# STM32F103_MCU.net
KiCad netlist of a schematic drawn in Altium Designer
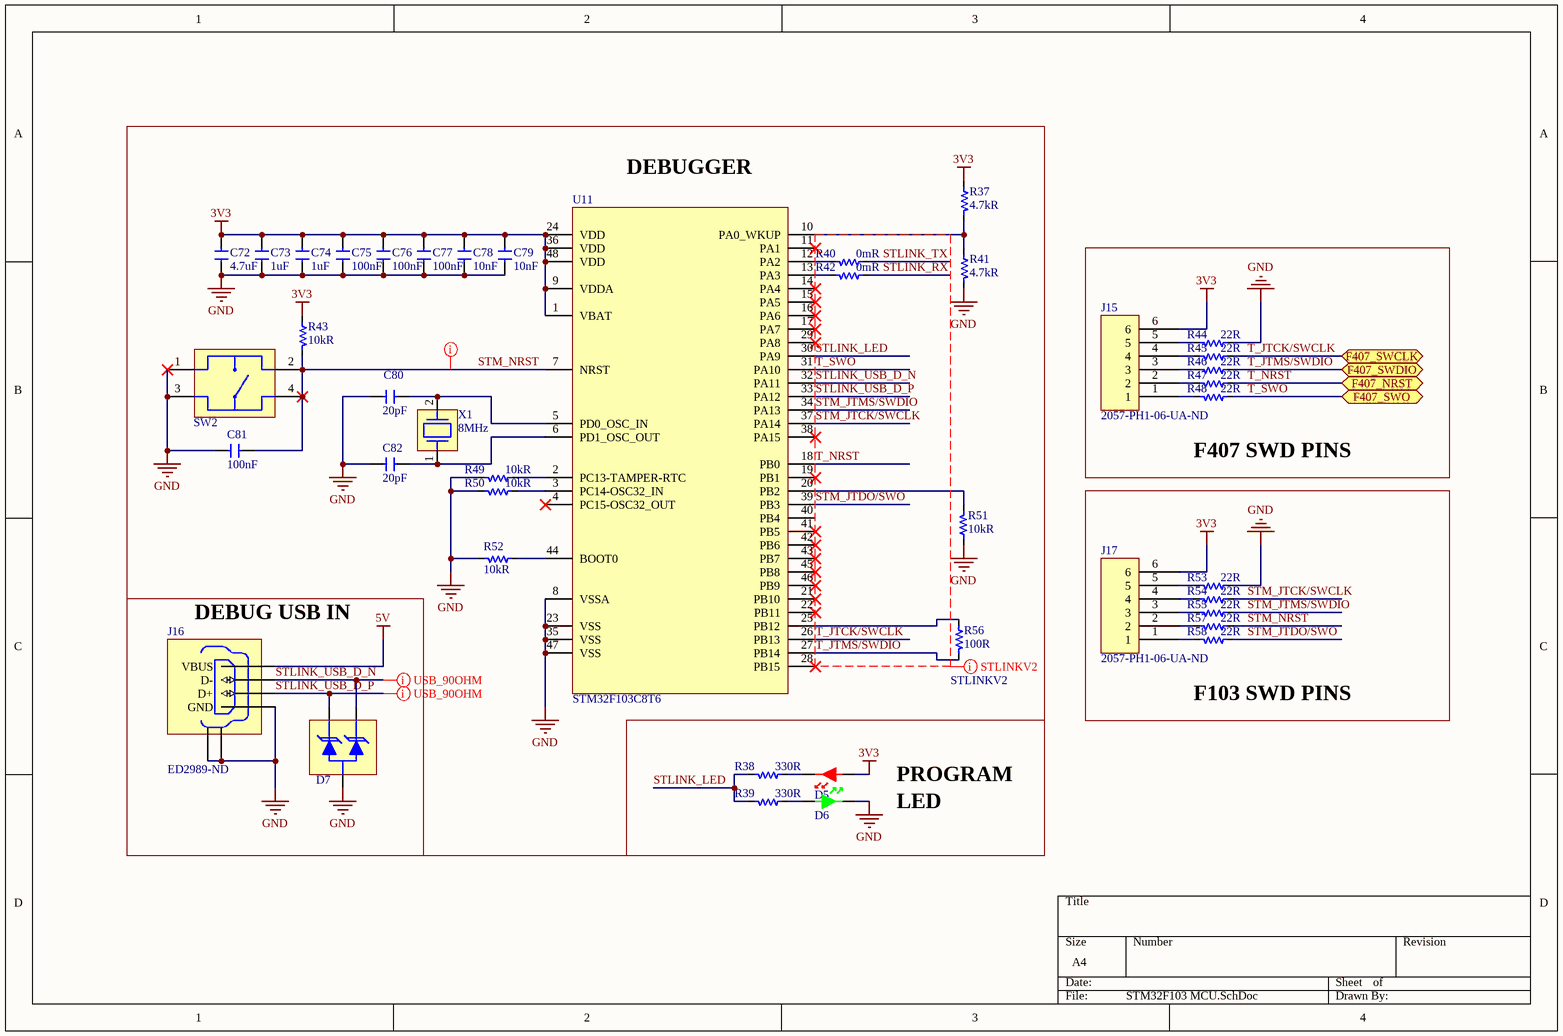
[diagram p0: STM32F103 MCU.SchDoc]

(export (version "E")
  (design (tool "Eeschema 10.0.6"))
  (components
    (comp (ref "C72")
      (value "CAP_4.7uF_%10_0805_25V_X7R_CER")
      (footprint "0805_CAP")
      (description "Cap 4.7UF 25VDC X7R 10% SMD 0805 Embossed Tape")
      (fields
        (field (name "MANUFACTURER") "Murata")
        (field (name "MANUFACTURER PART NUMBER") "GRM21BZ71E475KE15L")
        (field (name "CAPACITANCE") "4.7uF")
      )
      (libsource (lib "Main Schematic Library") (part "CAP_4.7uF_%10_0805_25V_X7R_CER"))
    )
    (comp (ref "C73")
      (value "1uF")
      (footprint "0805_CAP")
      (description "陶瓷电容 1uF(105) 1uF ±10% 25V 0805")
      (fields
        (field (name "MANUFACTURER") "Samsung")
        (field (name "MANUFACTURER PART NUMBER") "CL21B105KAFNNNG")
      )
      (libsource (lib "Main Schematic Library") (part "CAP_1uF_%10_25V_0805_X7R_CER"))
    )
    (comp (ref "C74")
      (value "1uF")
      (footprint "0805_CAP")
      (description "陶瓷电容 1uF(105) 1uF ±10% 25V 0805")
      (fields
        (field (name "MANUFACTURER") "Samsung")
        (field (name "MANUFACTURER PART NUMBER") "CL21B105KAFNNNG")
      )
      (libsource (lib "Main Schematic Library") (part "CAP_1uF_%10_25V_0805_X7R_CER"))
    )
    (comp (ref "C75")
      (value "CAP_0.1uF_%20_50V_0805_X7R_CER")
      (footprint "0805_CAP")
      (description "Cap Ceramic 0.1uF 50V X7R 20% SMD 0805 125C Paper T/R")
      (fields
        (field (name "MANUFACTURER") "KEMET")
        (field (name "MANUFACTURER PART NUMBER") "C0805C104M5RACTU")
        (field (name "CAPACITANCE") "100nF")
      )
      (libsource (lib "Main Schematic Library") (part "CAP_0.1uF_%20_50V_0805_X7R_CER"))
    )
    (comp (ref "C76")
      (value "CAP_0.1uF_%20_50V_0805_X7R_CER")
      (footprint "0805_CAP")
      (description "Cap Ceramic 0.1uF 50V X7R 20% SMD 0805 125C Paper T/R")
      (fields
        (field (name "MANUFACTURER") "KEMET")
        (field (name "MANUFACTURER PART NUMBER") "C0805C104M5RACTU")
        (field (name "CAPACITANCE") "100nF")
      )
      (libsource (lib "Main Schematic Library") (part "CAP_0.1uF_%20_50V_0805_X7R_CER"))
    )
    (comp (ref "C77")
      (value "CAP_0.1uF_%20_50V_0805_X7R_CER")
      (footprint "0805_CAP")
      (description "Cap Ceramic 0.1uF 50V X7R 20% SMD 0805 125C Paper T/R")
      (fields
        (field (name "MANUFACTURER") "KEMET")
        (field (name "MANUFACTURER PART NUMBER") "C0805C104M5RACTU")
        (field (name "CAPACITANCE") "100nF")
      )
      (libsource (lib "Main Schematic Library") (part "CAP_0.1uF_%20_50V_0805_X7R_CER"))
    )
    (comp (ref "C78")
      (value "CAP_10nF_%10_50V_0805_X7R_CER")
      (footprint "0805_CAP")
      (description "CAP CER 10000PF 50V X7R 0805")
      (fields
        (field (name "MANUFACTURER") "Samsung")
        (field (name "MANUFACTURER PART NUMBER") "CL21B103KBANNNC")
        (field (name "CAPACITANCE") "10nF")
      )
      (libsource (lib "Main Schematic Library") (part "CAP_10nF_%10_50V_0805_X7R_CER"))
    )
    (comp (ref "C79")
      (value "CAP_10nF_%10_50V_0805_X7R_CER")
      (footprint "0805_CAP")
      (description "CAP CER 10000PF 50V X7R 0805")
      (fields
        (field (name "MANUFACTURER") "Samsung")
        (field (name "MANUFACTURER PART NUMBER") "CL21B103KBANNNC")
        (field (name "CAPACITANCE") "10nF")
      )
      (libsource (lib "Main Schematic Library") (part "CAP_10nF_%10_50V_0805_X7R_CER"))
    )
    (comp (ref "C80")
      (value "CAP_20pF_5%_50V_0805_C0G/NP0_CER")
      (footprint "0805_CAP")
      (description "CAP CER 20PF 50V C0G/NP0 0805")
      (fields
        (field (name "MANUFACTURER") "Samsung")
        (field (name "MANUFACTURER PART NUMBER") "CL21C200JBANNNC")
        (field (name "CAPACITANCE") "20pF")
      )
      (libsource (lib "Main Schematic Library") (part "CAP_20pF_5%_50V_0805_C0G/NP0_CER"))
    )
    (comp (ref "C81")
      (value "CAP_100nF_50V_0805_C0G_CER")
      (footprint "0805_CAP")
      (description "Cap Ceramic 0.1uF 50V X7R 20% SMD 0805 125C Paper T/R")
      (fields
        (field (name "MANUFACTURER") "KEMET")
        (field (name "MANUFACTURER PART NUMBER") "C0805C104M5RACTU")
        (field (name "CAPACITANCE") "100nF")
      )
      (libsource (lib "Main Schematic Library") (part "CAP_100nF_50V_0805_C0G_CER"))
    )
    (comp (ref "C82")
      (value "CAP_20pF_5%_50V_0805_C0G/NP0_CER")
      (footprint "0805_CAP")
      (description "CAP CER 20PF 50V C0G/NP0 0805")
      (fields
        (field (name "MANUFACTURER") "Samsung")
        (field (name "MANUFACTURER PART NUMBER") "CL21C200JBANNNC")
        (field (name "CAPACITANCE") "20pF")
      )
      (libsource (lib "Main Schematic Library") (part "CAP_20pF_5%_50V_0805_C0G/NP0_CER"))
    )
    (comp (ref "D5")
      (value "Red")
      (footprint "DIOC2114X07N-0805-LED-RED")
      (description "Led Red Clear 2SMD")
      (fields
        (field (name "MANUFACTURER") "Everlight")
        (field (name "MANUFACTURER PART NUMBER") "EAST2012RA1")
      )
      (libsource (lib "Main Schematic Library") (part "LED_RED CLEAR_2SMD/0805"))
    )
    (comp (ref "D6")
      (value "Green")
      (footprint "DIOC2114X07N-0805-LED-GREEN")
      (description "Led Green Clear 2SMD")
      (fields
        (field (name "MANUFACTURER") "Everlight")
        (field (name "MANUFACTURER PART NUMBER") "EAST2012GA5")
      )
      (libsource (lib "Main Schematic Library") (part "LED_GREEN CLEAR_2SMD/0805"))
    )
    (comp (ref "D7")
      (value "DIODE_TVS_3.3VWM_8VC_SOT23")
      (footprint "SOT170P237X110-3N")
      (description "ESD Suppressor TVS Uni-Dir 3.3V 3-Pin SOT-23 T/R")
      (fields (field (name "MANUFACTURER") "MCC") (field (name "MANUFACTURER PART NUMBER") "ESD3V3AP-TP"))
      (libsource (lib "Main Schematic Library") (part "DIODE_TVS_3.3VWM_8VC_SOT23"))
    )
    (comp (ref "J15")
      (value "CONN_1X6_2.54m_Male Header")
      (footprint "DIP_1X6_MALE_HEADER_2.54_PITCH")
      (description "PH Series 6 Position Through Hole Single Row Straight .100 Header")
      (fields
        (field (name "MANUFACTURER") "Adam Equipment")
        (field (name "MANUFACTURER PART NUMBER") "PH1-06-UA")
        (field (name "SUPPLIER PART NUMBER 1") "2057-PH1-06-UA-ND")
      )
      (libsource (lib "Main Schematic Library") (part "CONN_1X6_2.54m_Male Header"))
    )
    (comp (ref "J16")
      (value "CONN_RCPT_USB-TYPE A_A1HSW6")
      (footprint "USB_2.0_B_OST_USB-A1HSW6")
      (description "USB - A Receptacle Connector 4 Position Through Hole, Right Angle")
      (fields
        (field (name "MP") "USB-A1HSW6")
        (field (name "MF") "{'manufacturer': u'On Shore'}")
        (field (name "SUPPLIER PART NUMBER 1") "ED2989-ND")
      )
      (libsource (lib "Main Schematic Library") (part "CONN_RCPT_USB-TYPE A_A1HSW6"))
    )
    (comp (ref "J17")
      (value "CONN_1X6_2.54m_Male Header")
      (footprint "DIP_1X6_MALE_HEADER_2.54_PITCH")
      (description "PH Series 6 Position Through Hole Single Row Straight .100 Header")
      (fields
        (field (name "MANUFACTURER") "Adam Equipment")
        (field (name "MANUFACTURER PART NUMBER") "PH1-06-UA")
        (field (name "SUPPLIER PART NUMBER 1") "2057-PH1-06-UA-ND")
      )
      (libsource (lib "Main Schematic Library") (part "CONN_1X6_2.54m_Male Header"))
    )
    (comp (ref "R37")
      (value "RES_4.7K OHM_5%_1/8W_0805")
      (footprint "0805_RES")
      (description "Res Thick Film 0805 4.7K Ohm 5% 1/8W ±200ppm/°C Molded SMD Paper T/R")
      (fields
        (field (name "MANUFACTURER") "Vishay")
        (field (name "MANUFACTURER PART NUMBER") "CRCW08054K70JNEAC")
        (field (name "RESISTANCE") "4.7kR")
      )
      (libsource (lib "Main Schematic Library") (part "RES_4.7K OHM_5%_1/8W_0805"))
    )
    (comp (ref "R38")
      (value "RES_330 OHM_5%_0805_1/8W")
      (footprint "0805_RES")
      (description "Res Thick Film 0805 330 Ohm 5% 0.125W(1/8W) ±100ppm/C Pad SMD Automotive T/R")
      (fields
        (field (name "MANUFACTURER") "TE Connectivity")
        (field (name "MANUFACTURER PART NUMBER") "CRGCQ0805J330R")
        (field (name "RESISTANCE") "330R")
      )
      (libsource (lib "Main Schematic Library") (part "RES_330 OHM_5%_0805_1/8W"))
    )
    (comp (ref "R39")
      (value "RES_330 OHM_5%_0805_1/8W")
      (footprint "0805_RES")
      (description "Res Thick Film 0805 330 Ohm 5% 0.125W(1/8W) ±100ppm/C Pad SMD Automotive T/R")
      (fields
        (field (name "MANUFACTURER") "TE Connectivity")
        (field (name "MANUFACTURER PART NUMBER") "CRGCQ0805J330R")
        (field (name "RESISTANCE") "330R")
      )
      (libsource (lib "Main Schematic Library") (part "RES_330 OHM_5%_0805_1/8W"))
    )
    (comp (ref "R40")
      (value "RES_0 OHM_JUMPER_0805_1/8W")
      (footprint "0805_RES")
      (description "贴片电阻 0Ω ±5% 1/8W 0805")
      (fields
        (field (name "MANUFACTURER") "Yageo")
        (field (name "MANUFACTURER PART NUMBER") "RC0805JR-070RL")
        (field (name "RESISTANCE") "0mR")
      )
      (libsource (lib "Main Schematic Library") (part "RES_0 OHM_JUMPER_0805_1/8W"))
    )
    (comp (ref "R41")
      (value "RES_4.7K OHM_5%_1/8W_0805")
      (footprint "0805_RES")
      (description "Res Thick Film 0805 4.7K Ohm 5% 1/8W ±200ppm/°C Molded SMD Paper T/R")
      (fields
        (field (name "MANUFACTURER") "Vishay")
        (field (name "MANUFACTURER PART NUMBER") "CRCW08054K70JNEAC")
        (field (name "RESISTANCE") "4.7kR")
      )
      (libsource (lib "Main Schematic Library") (part "RES_4.7K OHM_5%_1/8W_0805"))
    )
    (comp (ref "R42")
      (value "RES_0 OHM_JUMPER_0805_1/8W")
      (footprint "0805_RES")
      (description "贴片电阻 0Ω ±5% 1/8W 0805")
      (fields
        (field (name "MANUFACTURER") "Yageo")
        (field (name "MANUFACTURER PART NUMBER") "RC0805JR-070RL")
        (field (name "RESISTANCE") "0mR")
      )
      (libsource (lib "Main Schematic Library") (part "RES_0 OHM_JUMPER_0805_1/8W"))
    )
    (comp (ref "R43")
      (value "10k Ohms")
      (footprint "0805_RES")
      (description "Res SMD 0805 10K 1% 0.125W T.C.100PPM")
      (fields
        (field (name "MANUFACTURER") "TDK")
        (field (name "MANUFACTURER PART NUMBER") "C2012X7R1H104K085AA")
        (field (name "RESISTANCE") "10kR")
      )
      (libsource (lib "Main Schematic Library") (part "RES_10K OHM_%1_0805_1/8W"))
    )
    (comp (ref "R44")
      (value "RES_22 OHM_1%_1/8W_0805")
      (footprint "0805_RES")
      (description "Res Thick Film 0805 22 Ohm 1% 0.125W(1/8W) ±100ppm/C Pad SMD T/R")
      (fields
        (field (name "MANUFACTURER") "Vishay Dale")
        (field (name "MANUFACTURER PART NUMBER") "CRCW080522R0FKEAC")
        (field (name "RESISTANCE") "22R")
      )
      (libsource (lib "Main Schematic Library") (part "RES_22 OHM_1%_1/8W_0805"))
    )
    (comp (ref "R45")
      (value "RES_22 OHM_1%_1/8W_0805")
      (footprint "0805_RES")
      (description "Res Thick Film 0805 22 Ohm 1% 0.125W(1/8W) ±100ppm/C Pad SMD T/R")
      (fields
        (field (name "MANUFACTURER") "Vishay Dale")
        (field (name "MANUFACTURER PART NUMBER") "CRCW080522R0FKEAC")
        (field (name "RESISTANCE") "22R")
      )
      (libsource (lib "Main Schematic Library") (part "RES_22 OHM_1%_1/8W_0805"))
    )
    (comp (ref "R46")
      (value "RES_22 OHM_1%_1/8W_0805")
      (footprint "0805_RES")
      (description "Res Thick Film 0805 22 Ohm 1% 0.125W(1/8W) ±100ppm/C Pad SMD T/R")
      (fields
        (field (name "MANUFACTURER") "Vishay Dale")
        (field (name "MANUFACTURER PART NUMBER") "CRCW080522R0FKEAC")
        (field (name "RESISTANCE") "22R")
      )
      (libsource (lib "Main Schematic Library") (part "RES_22 OHM_1%_1/8W_0805"))
    )
    (comp (ref "R47")
      (value "RES_22 OHM_1%_1/8W_0805")
      (footprint "0805_RES")
      (description "Res Thick Film 0805 22 Ohm 1% 0.125W(1/8W) ±100ppm/C Pad SMD T/R")
      (fields
        (field (name "MANUFACTURER") "Vishay Dale")
        (field (name "MANUFACTURER PART NUMBER") "CRCW080522R0FKEAC")
        (field (name "RESISTANCE") "22R")
      )
      (libsource (lib "Main Schematic Library") (part "RES_22 OHM_1%_1/8W_0805"))
    )
    (comp (ref "R48")
      (value "RES_22 OHM_1%_1/8W_0805")
      (footprint "0805_RES")
      (description "Res Thick Film 0805 22 Ohm 1% 0.125W(1/8W) ±100ppm/C Pad SMD T/R")
      (fields
        (field (name "MANUFACTURER") "Vishay Dale")
        (field (name "MANUFACTURER PART NUMBER") "CRCW080522R0FKEAC")
        (field (name "RESISTANCE") "22R")
      )
      (libsource (lib "Main Schematic Library") (part "RES_22 OHM_1%_1/8W_0805"))
    )
    (comp (ref "R49")
      (value "10k Ohms")
      (footprint "0805_RES")
      (description "Res SMD 0805 10K 1% 0.125W T.C.100PPM")
      (fields
        (field (name "MANUFACTURER") "TDK")
        (field (name "MANUFACTURER PART NUMBER") "C2012X7R1H104K085AA")
        (field (name "RESISTANCE") "10kR")
      )
      (libsource (lib "Main Schematic Library") (part "RES_10K OHM_%1_0805_1/8W"))
    )
    (comp (ref "R50")
      (value "10k Ohms")
      (footprint "0805_RES")
      (description "Res SMD 0805 10K 1% 0.125W T.C.100PPM")
      (fields
        (field (name "MANUFACTURER") "TDK")
        (field (name "MANUFACTURER PART NUMBER") "C2012X7R1H104K085AA")
        (field (name "RESISTANCE") "10kR")
      )
      (libsource (lib "Main Schematic Library") (part "RES_10K OHM_%1_0805_1/8W"))
    )
    (comp (ref "R51")
      (value "10k Ohms")
      (footprint "0805_RES")
      (description "Res SMD 0805 10K 1% 0.125W T.C.100PPM")
      (fields
        (field (name "MANUFACTURER") "TDK")
        (field (name "MANUFACTURER PART NUMBER") "C2012X7R1H104K085AA")
        (field (name "RESISTANCE") "10kR")
      )
      (libsource (lib "Main Schematic Library") (part "RES_10K OHM_%1_0805_1/8W"))
    )
    (comp (ref "R52")
      (value "10k Ohms")
      (footprint "0805_RES")
      (description "Res SMD 0805 10K 1% 0.125W T.C.100PPM")
      (fields
        (field (name "MANUFACTURER") "TDK")
        (field (name "MANUFACTURER PART NUMBER") "C2012X7R1H104K085AA")
        (field (name "RESISTANCE") "10kR")
      )
      (libsource (lib "Main Schematic Library") (part "RES_10K OHM_%1_0805_1/8W"))
    )
    (comp (ref "R53")
      (value "RES_22 OHM_1%_1/8W_0805")
      (footprint "0805_RES")
      (description "Res Thick Film 0805 22 Ohm 1% 0.125W(1/8W) ±100ppm/C Pad SMD T/R")
      (fields
        (field (name "MANUFACTURER") "Vishay Dale")
        (field (name "MANUFACTURER PART NUMBER") "CRCW080522R0FKEAC")
        (field (name "RESISTANCE") "22R")
      )
      (libsource (lib "Main Schematic Library") (part "RES_22 OHM_1%_1/8W_0805"))
    )
    (comp (ref "R54")
      (value "RES_22 OHM_1%_1/8W_0805")
      (footprint "0805_RES")
      (description "Res Thick Film 0805 22 Ohm 1% 0.125W(1/8W) ±100ppm/C Pad SMD T/R")
      (fields
        (field (name "MANUFACTURER") "Vishay Dale")
        (field (name "MANUFACTURER PART NUMBER") "CRCW080522R0FKEAC")
        (field (name "RESISTANCE") "22R")
      )
      (libsource (lib "Main Schematic Library") (part "RES_22 OHM_1%_1/8W_0805"))
    )
    (comp (ref "R55")
      (value "RES_22 OHM_1%_1/8W_0805")
      (footprint "0805_RES")
      (description "Res Thick Film 0805 22 Ohm 1% 0.125W(1/8W) ±100ppm/C Pad SMD T/R")
      (fields
        (field (name "MANUFACTURER") "Vishay Dale")
        (field (name "MANUFACTURER PART NUMBER") "CRCW080522R0FKEAC")
        (field (name "RESISTANCE") "22R")
      )
      (libsource (lib "Main Schematic Library") (part "RES_22 OHM_1%_1/8W_0805"))
    )
    (comp (ref "R56")
      (value "RES_100 OHM_1%_0805_1/8W")
      (footprint "0805_RES")
      (description "贴片电阻 100Ω ± 1.00% 0.125W ± 100ppm/℃ 0805")
      (fields
        (field (name "MANUFACTURER") "Yageo")
        (field (name "MANUFACTURER PART NUMBER") "RC0805FR-07100RL")
        (field (name "RESISTANCE") "100R")
      )
      (libsource (lib "Main Schematic Library") (part "RES_100 OHM_1%_0805_1/8W"))
    )
    (comp (ref "R57")
      (value "RES_22 OHM_1%_1/8W_0805")
      (footprint "0805_RES")
      (description "Res Thick Film 0805 22 Ohm 1% 0.125W(1/8W) ±100ppm/C Pad SMD T/R")
      (fields
        (field (name "MANUFACTURER") "Vishay Dale")
        (field (name "MANUFACTURER PART NUMBER") "CRCW080522R0FKEAC")
        (field (name "RESISTANCE") "22R")
      )
      (libsource (lib "Main Schematic Library") (part "RES_22 OHM_1%_1/8W_0805"))
    )
    (comp (ref "R58")
      (value "RES_22 OHM_1%_1/8W_0805")
      (footprint "0805_RES")
      (description "Res Thick Film 0805 22 Ohm 1% 0.125W(1/8W) ±100ppm/C Pad SMD T/R")
      (fields
        (field (name "MANUFACTURER") "Vishay Dale")
        (field (name "MANUFACTURER PART NUMBER") "CRCW080522R0FKEAC")
        (field (name "RESISTANCE") "22R")
      )
      (libsource (lib "Main Schematic Library") (part "RES_22 OHM_1%_1/8W_0805"))
    )
    (comp (ref "SW2")
      (value "SWITCH_TACTILE_SPST-NO_0.05A_12V")
      (footprint "TACT_SWITCH_6MMX6MM")
      (description "Switch Tactile N.O. SPST Round Button Gull Wing 0.05A 12VDC 100000Cycles 1.27N SMD T/R")
      (fields
        (field (name "MANUFACTURER") "ITT C&K")
        (field (name "MANUFACTURER PART NUMBER") "PTS645SL43SMTR92LFS")
      )
      (libsource (lib "Main Schematic Library") (part "SWITCH_TACTILE_SPST-NO_0.05A_12V"))
    )
    (comp (ref "U11")
      (value "STM32F103C8T6")
      (footprint "QFP50P900X900X160-48N")
      (description "IC MCU 32BIT 64KB FLASH 48LQFP")
      (fields (field (name "MANUFACTURER") "STMicroelectronics"))
      (libsource (lib "Main Schematic Library") (part "IC_MCU_STM32F103C8T6"))
    )
    (comp (ref "X1")
      (value "8MHz")
      (footprint "HC-49/US")
      (description "Crystal 8.0000MHZ 16PF SMD")
      (fields
        (field (name "MANUFACTURER") "Raltron Electronics")
        (field (name "MANUFACTURER PART NUMBER") "AS-8.000-16-SMD-TR")
      )
      (libsource (lib "Main Schematic Library") (part "CRYSTAL_8.0000MHZ_16PF_SMD"))
    )
  )
  (nets
    (net (code "1") (name "/STLINK_LED") (class "Default")
      (node (ref "R38") (pin "1") (pinfunction "1_1") (pintype "passive"))
      (node (ref "R39") (pin "1") (pinfunction "1_1") (pintype "passive"))
      (node (ref "U11") (pin "30") (pinfunction "PA9_30") (pintype "passive"))
    )
    (net (code "2") (name "/STLINK_RX") (class "Default")
      (node (ref "R42") (pin "2") (pinfunction "2_2") (pintype "passive"))
    )
    (net (code "3") (name "/STLINK_TX") (class "Default")
      (node (ref "R40") (pin "2") (pinfunction "2_2") (pintype "passive"))
    )
    (net (code "4") (name "/STLINK_USB_D_N") (class "Default")
      (node (ref "D7") (pin "1") (pinfunction "CATHODE_1_1") (pintype "passive"))
      (node (ref "J16") (pin "2") (pinfunction "D-_2") (pintype "bidirectional"))
      (node (ref "U11") (pin "32") (pinfunction "PA11_32") (pintype "passive"))
    )
    (net (code "5") (name "/STLINK_USB_D_P") (class "Default")
      (node (ref "D7") (pin "2") (pinfunction "CATHODE_2_2") (pintype "passive"))
      (node (ref "J16") (pin "3") (pinfunction "D+_3") (pintype "bidirectional"))
      (node (ref "U11") (pin "33") (pinfunction "PA12_33") (pintype "passive"))
    )
    (net (code "6") (name "/STM_JTCK{slash}SWCLK") (class "Default")
      (node (ref "R54") (pin "2") (pinfunction "2_2") (pintype "passive"))
      (node (ref "U11") (pin "37") (pinfunction "PA14_37") (pintype "passive"))
    )
    (net (code "7") (name "/STM_JTDO{slash}SWO") (class "Default")
      (node (ref "R58") (pin "2") (pinfunction "2_2") (pintype "passive"))
      (node (ref "U11") (pin "39") (pinfunction "PB3_39") (pintype "passive"))
    )
    (net (code "8") (name "/STM_JTMS{slash}SWDIO") (class "Default")
      (node (ref "R55") (pin "2") (pinfunction "2_2") (pintype "passive"))
      (node (ref "U11") (pin "34") (pinfunction "PA13_34") (pintype "passive"))
    )
    (net (code "9") (name "/STM_NRST") (class "Default")
      (node (ref "C81") (pin "1") (pinfunction "1_1") (pintype "passive"))
      (node (ref "R43") (pin "1") (pinfunction "1_1") (pintype "passive"))
      (node (ref "R57") (pin "2") (pinfunction "2_2") (pintype "passive"))
      (node (ref "SW2") (pin "2") (pinfunction "2_2") (pintype "passive"))
      (node (ref "SW2") (pin "4") (pinfunction "4_4") (pintype "passive"))
      (node (ref "U11") (pin "7") (pinfunction "NRST_7") (pintype "passive"))
    )
    (net (code "10") (name "/T_JTCK{slash}SWCLK") (class "Default")
      (node (ref "R45") (pin "2") (pinfunction "2_2") (pintype "passive"))
      (node (ref "U11") (pin "26") (pinfunction "PB13_26") (pintype "passive"))
    )
    (net (code "11") (name "/T_JTMS{slash}SWDIO") (class "Default")
      (node (ref "R46") (pin "2") (pinfunction "2_2") (pintype "passive"))
      (node (ref "R56") (pin "1") (pinfunction "1_1") (pintype "passive"))
      (node (ref "U11") (pin "27") (pinfunction "PB14_27") (pintype "passive"))
    )
    (net (code "12") (name "/T_NRST") (class "Default")
      (node (ref "R47") (pin "2") (pinfunction "2_2") (pintype "passive"))
      (node (ref "U11") (pin "18") (pinfunction "PB0_18") (pintype "passive"))
    )
    (net (code "13") (name "/T_SWO") (class "Default")
      (node (ref "R48") (pin "2") (pinfunction "2_2") (pintype "passive"))
      (node (ref "U11") (pin "31") (pinfunction "PA10_31") (pintype "passive"))
    )
    (net (code "14") (name "3V3") (class "Default")
      (node (ref "C72") (pin "2") (pinfunction "2_2") (pintype "passive"))
      (node (ref "C73") (pin "2") (pinfunction "2_2") (pintype "passive"))
      (node (ref "C74") (pin "2") (pinfunction "2_2") (pintype "passive"))
      (node (ref "C75") (pin "2") (pinfunction "2_2") (pintype "passive"))
      (node (ref "C76") (pin "2") (pinfunction "2_2") (pintype "passive"))
      (node (ref "C77") (pin "2") (pinfunction "2_2") (pintype "passive"))
      (node (ref "C78") (pin "2") (pinfunction "2_2") (pintype "passive"))
      (node (ref "C79") (pin "2") (pinfunction "2_2") (pintype "passive"))
      (node (ref "D5") (pin "2") (pinfunction "ANODE_2") (pintype "passive"))
      (node (ref "J15") (pin "6") (pinfunction "6_6") (pintype "passive"))
      (node (ref "J17") (pin "6") (pinfunction "6_6") (pintype "passive"))
      (node (ref "R37") (pin "2") (pinfunction "2_2") (pintype "passive"))
      (node (ref "R43") (pin "2") (pinfunction "2_2") (pintype "passive"))
      (node (ref "U11") (pin "1") (pinfunction "VBAT_1") (pintype "passive"))
      (node (ref "U11") (pin "24") (pinfunction "VDD_24") (pintype "passive"))
      (node (ref "U11") (pin "36") (pinfunction "VDD_36") (pintype "passive"))
      (node (ref "U11") (pin "48") (pinfunction "VDD_48") (pintype "passive"))
      (node (ref "U11") (pin "9") (pinfunction "VDDA_9") (pintype "passive"))
    )
    (net (code "15") (name "5V") (class "Default")
      (node (ref "J16") (pin "1") (pinfunction "VBUS_1") (pintype "power_in"))
    )
    (net (code "16") (name "GND") (class "Default")
      (node (ref "C72") (pin "1") (pinfunction "1_1") (pintype "passive"))
      (node (ref "C73") (pin "1") (pinfunction "1_1") (pintype "passive"))
      (node (ref "C74") (pin "1") (pinfunction "1_1") (pintype "passive"))
      (node (ref "C75") (pin "1") (pinfunction "1_1") (pintype "passive"))
      (node (ref "C76") (pin "1") (pinfunction "1_1") (pintype "passive"))
      (node (ref "C77") (pin "1") (pinfunction "1_1") (pintype "passive"))
      (node (ref "C78") (pin "1") (pinfunction "1_1") (pintype "passive"))
      (node (ref "C79") (pin "1") (pinfunction "1_1") (pintype "passive"))
      (node (ref "C80") (pin "1") (pinfunction "1_1") (pintype "passive"))
      (node (ref "C81") (pin "2") (pinfunction "2_2") (pintype "passive"))
      (node (ref "C82") (pin "1") (pinfunction "1_1") (pintype "passive"))
      (node (ref "D6") (pin "1") (pinfunction "CATHODE_1") (pintype "passive"))
      (node (ref "D7") (pin "3") (pinfunction "ANODE_3") (pintype "passive"))
      (node (ref "J16") (pin "4") (pinfunction "GND_4") (pintype "power_in"))
      (node (ref "J16") (pin "SH1") (pinfunction "SHIELD_SH1") (pintype "power_in"))
      (node (ref "J16") (pin "SH2") (pinfunction "SHIELD_SH2") (pintype "power_in"))
      (node (ref "R41") (pin "1") (pinfunction "1_1") (pintype "passive"))
      (node (ref "R44") (pin "2") (pinfunction "2_2") (pintype "passive"))
      (node (ref "R49") (pin "1") (pinfunction "1_1") (pintype "passive"))
      (node (ref "R50") (pin "1") (pinfunction "1_1") (pintype "passive"))
      (node (ref "R51") (pin "2") (pinfunction "2_2") (pintype "passive"))
      (node (ref "R52") (pin "1") (pinfunction "1_1") (pintype "passive"))
      (node (ref "R53") (pin "2") (pinfunction "2_2") (pintype "passive"))
      (node (ref "SW2") (pin "1") (pinfunction "1_1") (pintype "passive"))
      (node (ref "SW2") (pin "3") (pinfunction "3_3") (pintype "passive"))
      (node (ref "U11") (pin "23") (pinfunction "VSS_23") (pintype "passive"))
      (node (ref "U11") (pin "35") (pinfunction "VSS_35") (pintype "passive"))
      (node (ref "U11") (pin "47") (pinfunction "VSS_47") (pintype "passive"))
      (node (ref "U11") (pin "8") (pinfunction "VSSA_8") (pintype "passive"))
    )
    (net (code "17") (name "Net-(D5-CATHODE)") (class "Default")
      (node (ref "D5") (pin "1") (pinfunction "CATHODE_1") (pintype "passive"))
      (node (ref "R38") (pin "2") (pinfunction "2_2") (pintype "passive"))
    )
    (net (code "18") (name "Net-(D6-ANODE)") (class "Default")
      (node (ref "D6") (pin "2") (pinfunction "ANODE_2") (pintype "passive"))
      (node (ref "R39") (pin "2") (pinfunction "2_2") (pintype "passive"))
    )
    (net (code "19") (name "Net-(J15-Pad1)") (class "Default")
      (node (ref "J15") (pin "1") (pinfunction "1_1") (pintype "passive"))
      (node (ref "R48") (pin "1") (pinfunction "1_1") (pintype "passive"))
    )
    (net (code "20") (name "Net-(J15-Pad2)") (class "Default")
      (node (ref "J15") (pin "2") (pinfunction "2_2") (pintype "passive"))
      (node (ref "R47") (pin "1") (pinfunction "1_1") (pintype "passive"))
    )
    (net (code "21") (name "Net-(J15-Pad3)") (class "Default")
      (node (ref "J15") (pin "3") (pinfunction "3_3") (pintype "passive"))
      (node (ref "R46") (pin "1") (pinfunction "1_1") (pintype "passive"))
    )
    (net (code "22") (name "Net-(J15-Pad4)") (class "Default")
      (node (ref "J15") (pin "4") (pinfunction "4_4") (pintype "passive"))
      (node (ref "R45") (pin "1") (pinfunction "1_1") (pintype "passive"))
    )
    (net (code "23") (name "Net-(J15-Pad5)") (class "Default")
      (node (ref "J15") (pin "5") (pinfunction "5_5") (pintype "passive"))
      (node (ref "R44") (pin "1") (pinfunction "1_1") (pintype "passive"))
    )
    (net (code "24") (name "Net-(J17-Pad1)") (class "Default")
      (node (ref "J17") (pin "1") (pinfunction "1_1") (pintype "passive"))
      (node (ref "R58") (pin "1") (pinfunction "1_1") (pintype "passive"))
    )
    (net (code "25") (name "Net-(J17-Pad2)") (class "Default")
      (node (ref "J17") (pin "2") (pinfunction "2_2") (pintype "passive"))
      (node (ref "R57") (pin "1") (pinfunction "1_1") (pintype "passive"))
    )
    (net (code "26") (name "Net-(J17-Pad3)") (class "Default")
      (node (ref "J17") (pin "3") (pinfunction "3_3") (pintype "passive"))
      (node (ref "R55") (pin "1") (pinfunction "1_1") (pintype "passive"))
    )
    (net (code "27") (name "Net-(J17-Pad4)") (class "Default")
      (node (ref "J17") (pin "4") (pinfunction "4_4") (pintype "passive"))
      (node (ref "R54") (pin "1") (pinfunction "1_1") (pintype "passive"))
    )
    (net (code "28") (name "Net-(J17-Pad5)") (class "Default")
      (node (ref "J17") (pin "5") (pinfunction "5_5") (pintype "passive"))
      (node (ref "R53") (pin "1") (pinfunction "1_1") (pintype "passive"))
    )
    (net (code "29") (name "Net-(U11-BOOT0)") (class "Default")
      (node (ref "R52") (pin "2") (pinfunction "2_2") (pintype "passive"))
      (node (ref "U11") (pin "44") (pinfunction "BOOT0_44") (pintype "passive"))
    )
    (net (code "30") (name "Net-(U11-PA0_WKUP)") (class "Default")
      (node (ref "R37") (pin "1") (pinfunction "1_1") (pintype "passive"))
      (node (ref "R41") (pin "2") (pinfunction "2_2") (pintype "passive"))
      (node (ref "U11") (pin "10") (pinfunction "PA0_WKUP_10") (pintype "passive"))
    )
    (net (code "31") (name "Net-(U11-PA2)") (class "Default")
      (node (ref "R40") (pin "1") (pinfunction "1_1") (pintype "passive"))
      (node (ref "U11") (pin "12") (pinfunction "PA2_12") (pintype "passive"))
    )
    (net (code "32") (name "Net-(U11-PA3)") (class "Default")
      (node (ref "R42") (pin "1") (pinfunction "1_1") (pintype "passive"))
      (node (ref "U11") (pin "13") (pinfunction "PA3_13") (pintype "passive"))
    )
    (net (code "33") (name "Net-(U11-PB2)") (class "Default")
      (node (ref "R51") (pin "1") (pinfunction "1_1") (pintype "passive"))
      (node (ref "U11") (pin "20") (pinfunction "PB2_20") (pintype "passive"))
    )
    (net (code "34") (name "Net-(U11-PB12)") (class "Default")
      (node (ref "R56") (pin "2") (pinfunction "2_2") (pintype "passive"))
      (node (ref "U11") (pin "25") (pinfunction "PB12_25") (pintype "passive"))
    )
    (net (code "35") (name "Net-(U11-PC13-TAMPER-RTC)") (class "Default")
      (node (ref "R49") (pin "2") (pinfunction "2_2") (pintype "passive"))
      (node (ref "U11") (pin "2") (pinfunction "PC13-TAMPER-RTC_2") (pintype "passive"))
    )
    (net (code "36") (name "Net-(U11-PC14-OSC32_IN)") (class "Default")
      (node (ref "R50") (pin "2") (pinfunction "2_2") (pintype "passive"))
      (node (ref "U11") (pin "3") (pinfunction "PC14-OSC32_IN_3") (pintype "passive"))
    )
    (net (code "37") (name "Net-(U11-PD0_OSC_IN)") (class "Default")
      (node (ref "C80") (pin "2") (pinfunction "2_2") (pintype "passive"))
      (node (ref "U11") (pin "5") (pinfunction "PD0_OSC_IN_5") (pintype "passive"))
      (node (ref "X1") (pin "2") (pinfunction "2_2") (pintype "passive"))
    )
    (net (code "38") (name "Net-(U11-PD1_OSC_OUT)") (class "Default")
      (node (ref "C82") (pin "2") (pinfunction "2_2") (pintype "passive"))
      (node (ref "U11") (pin "6") (pinfunction "PD1_OSC_OUT_6") (pintype "passive"))
      (node (ref "X1") (pin "1") (pinfunction "1_1") (pintype "passive"))
    )
    (net (code "39") (name "unconnected-(U11-PA1-Pad11)") (class "Default")
      (node (ref "U11") (pin "11") (pinfunction "PA1_11") (pintype "passive+no_connect"))
    )
    (net (code "40") (name "unconnected-(U11-PA4-Pad14)") (class "Default")
      (node (ref "U11") (pin "14") (pinfunction "PA4_14") (pintype "passive+no_connect"))
    )
    (net (code "41") (name "unconnected-(U11-PA5-Pad15)") (class "Default")
      (node (ref "U11") (pin "15") (pinfunction "PA5_15") (pintype "passive+no_connect"))
    )
    (net (code "42") (name "unconnected-(U11-PA6-Pad16)") (class "Default")
      (node (ref "U11") (pin "16") (pinfunction "PA6_16") (pintype "passive+no_connect"))
    )
    (net (code "43") (name "unconnected-(U11-PA7-Pad17)") (class "Default")
      (node (ref "U11") (pin "17") (pinfunction "PA7_17") (pintype "passive+no_connect"))
    )
    (net (code "44") (name "unconnected-(U11-PA8-Pad29)") (class "Default")
      (node (ref "U11") (pin "29") (pinfunction "PA8_29") (pintype "passive+no_connect"))
    )
    (net (code "45") (name "unconnected-(U11-PA15-Pad38)") (class "Default")
      (node (ref "U11") (pin "38") (pinfunction "PA15_38") (pintype "passive+no_connect"))
    )
    (net (code "46") (name "unconnected-(U11-PB1-Pad19)") (class "Default")
      (node (ref "U11") (pin "19") (pinfunction "PB1_19") (pintype "passive+no_connect"))
    )
    (net (code "47") (name "unconnected-(U11-PB4-Pad40)") (class "Default")
      (node (ref "U11") (pin "40") (pinfunction "PB4_40") (pintype "passive"))
    )
    (net (code "48") (name "unconnected-(U11-PB5-Pad41)") (class "Default")
      (node (ref "U11") (pin "41") (pinfunction "PB5_41") (pintype "passive+no_connect"))
    )
    (net (code "49") (name "unconnected-(U11-PB6-Pad42)") (class "Default")
      (node (ref "U11") (pin "42") (pinfunction "PB6_42") (pintype "passive+no_connect"))
    )
    (net (code "50") (name "unconnected-(U11-PB7-Pad43)") (class "Default")
      (node (ref "U11") (pin "43") (pinfunction "PB7_43") (pintype "passive+no_connect"))
    )
    (net (code "51") (name "unconnected-(U11-PB8-Pad45)") (class "Default")
      (node (ref "U11") (pin "45") (pinfunction "PB8_45") (pintype "passive+no_connect"))
    )
    (net (code "52") (name "unconnected-(U11-PB9-Pad46)") (class "Default")
      (node (ref "U11") (pin "46") (pinfunction "PB9_46") (pintype "passive+no_connect"))
    )
    (net (code "53") (name "unconnected-(U11-PB10-Pad21)") (class "Default")
      (node (ref "U11") (pin "21") (pinfunction "PB10_21") (pintype "passive+no_connect"))
    )
    (net (code "54") (name "unconnected-(U11-PB11-Pad22)") (class "Default")
      (node (ref "U11") (pin "22") (pinfunction "PB11_22") (pintype "passive+no_connect"))
    )
    (net (code "55") (name "unconnected-(U11-PB15-Pad28)") (class "Default")
      (node (ref "U11") (pin "28") (pinfunction "PB15_28") (pintype "passive+no_connect"))
    )
    (net (code "56") (name "unconnected-(U11-PC15-OSC32_OUT-Pad4)") (class "Default")
      (node (ref "U11") (pin "4") (pinfunction "PC15-OSC32_OUT_4") (pintype "passive+no_connect"))
    )
  )
)
